# Volt_Meter_PCB_Design.net
KiCad netlist of a schematic drawn in EAGLE
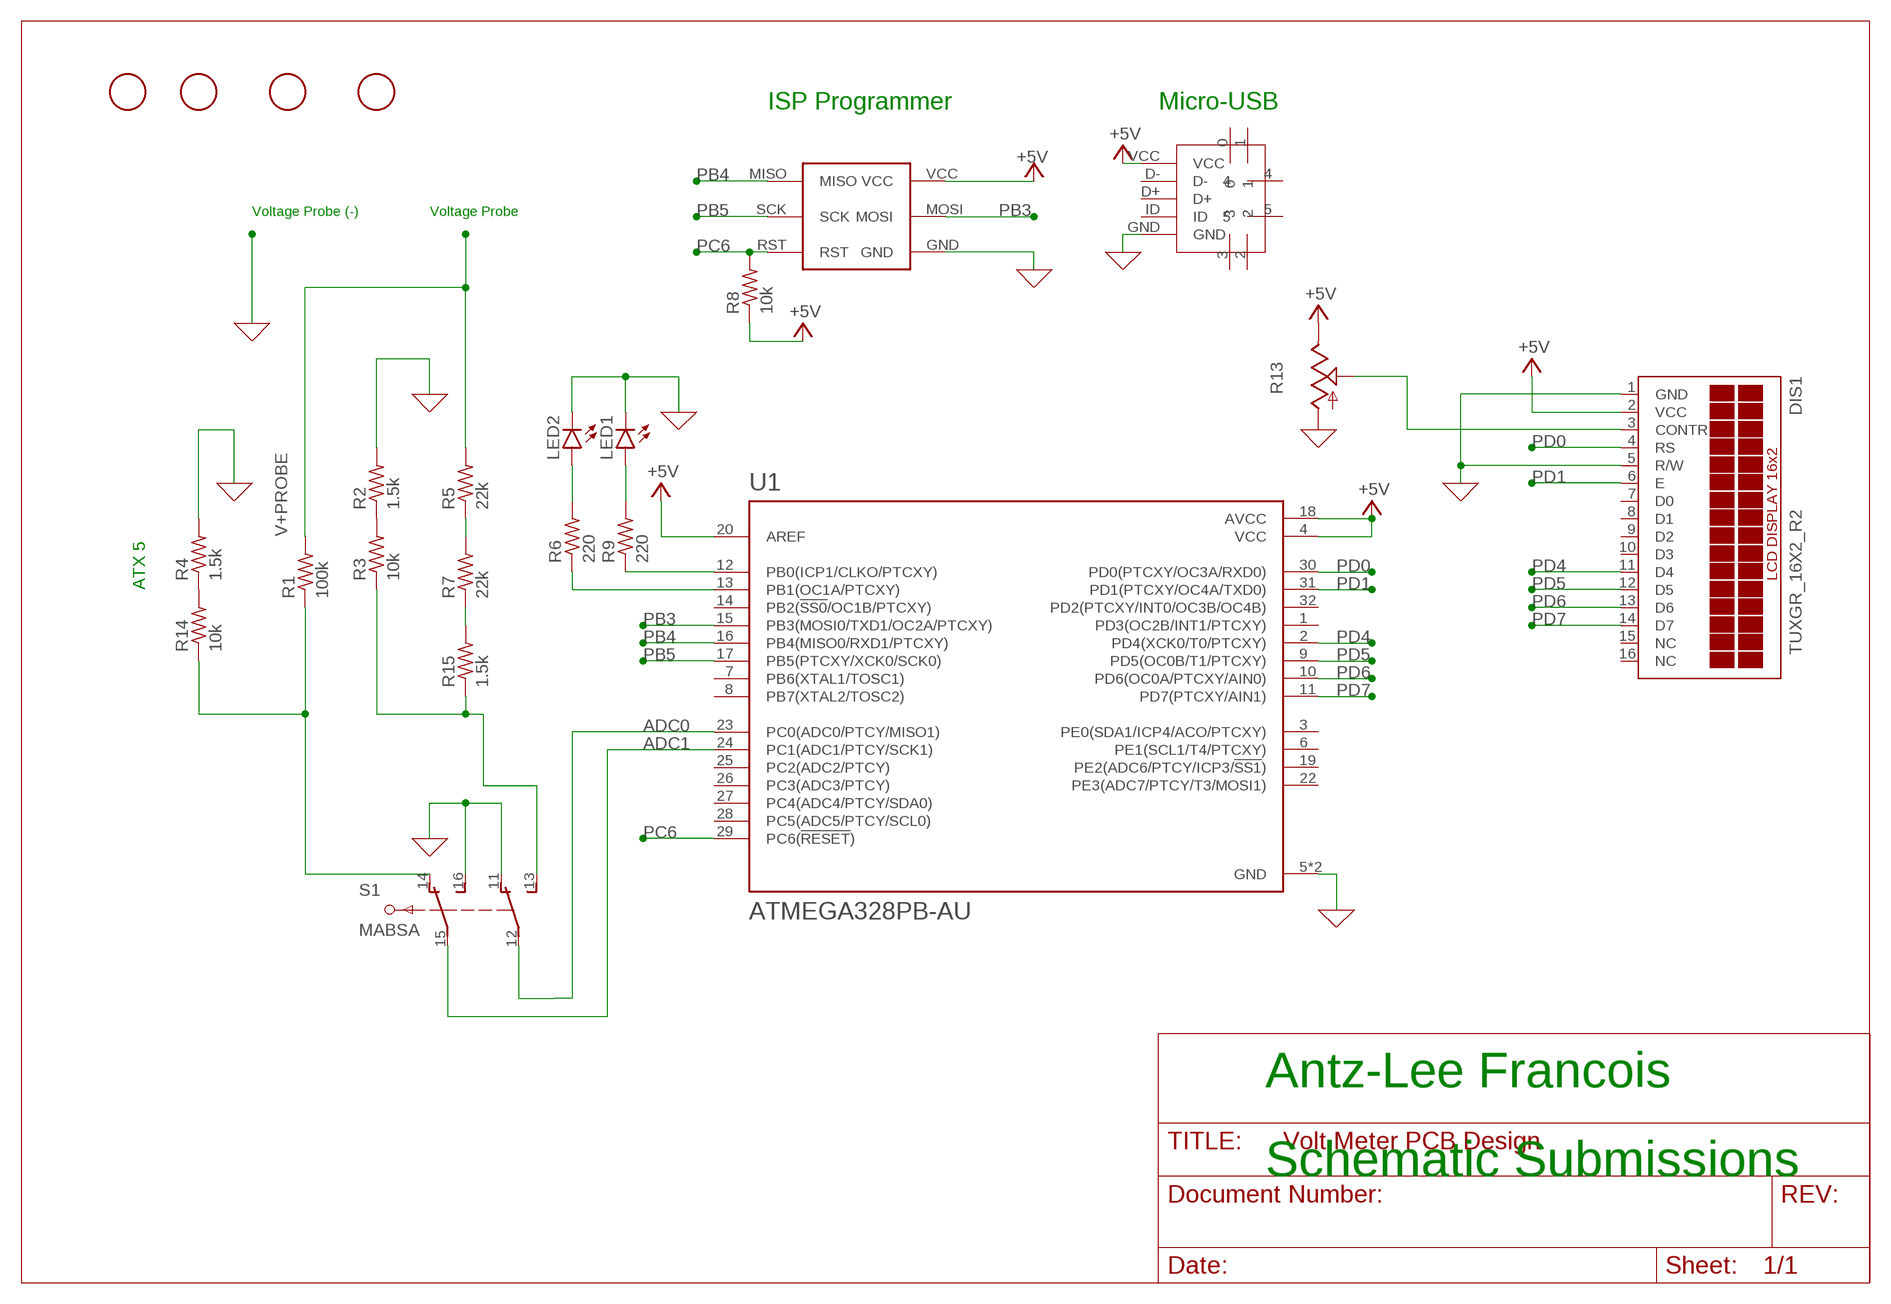
[diagram p0: schematic, sheet 1]

(export (version "E")
  (design (tool "Eeschema 10.0.6"))
  (components
    (comp (ref "AVR-ISP")
      (value "AVR-ISP")
      (footprint "eagle-import:AVR-ISP")
      (fields (field (name "MF") "Gravitech"))
      (libsource (lib "eagle-import") (part "AVR-ISP"))
    )
    (comp (ref "DIS1")
      (value "TUXGR_16X2_R2")
      (footprint "eagle-import:TUXGR_16X2_R2")
      (libsource (lib "eagle-import") (part "TUXGR_16X2_R2"))
    )
    (comp (ref "LED1")
      (value "LED5MM")
      (footprint "eagle-import:LED5MM")
      (libsource (lib "eagle-import") (part "LED5MM"))
    )
    (comp (ref "LED2")
      (value "LED5MM")
      (footprint "eagle-import:LED5MM")
      (libsource (lib "eagle-import") (part "LED5MM"))
    )
    (comp (ref "MICROUSB1")
      (value "MICROUSB1")
      (footprint "eagle-import:MICROUSB1")
      (libsource (lib "eagle-import") (part "MICROUSB1"))
    )
    (comp (ref "R1")
      (value "100k")
      (footprint "eagle-import:M0805")
      (libsource (lib "eagle-import") (part "R-US_M0805"))
    )
    (comp (ref "R2")
      (value "1.5k")
      (footprint "eagle-import:M0805")
      (libsource (lib "eagle-import") (part "R-US_M0805"))
    )
    (comp (ref "R3")
      (value "10k")
      (footprint "eagle-import:M0805")
      (libsource (lib "eagle-import") (part "R-US_M0805"))
    )
    (comp (ref "R4")
      (value "1.5k")
      (footprint "eagle-import:M0805")
      (libsource (lib "eagle-import") (part "R-US_M0805"))
    )
    (comp (ref "R5")
      (value "22k")
      (footprint "eagle-import:M0805")
      (libsource (lib "eagle-import") (part "R-US_M0805"))
    )
    (comp (ref "R6")
      (value "220")
      (footprint "eagle-import:M0805")
      (libsource (lib "eagle-import") (part "R-US_M0805"))
    )
    (comp (ref "R7")
      (value "22k")
      (footprint "eagle-import:M0805")
      (libsource (lib "eagle-import") (part "R-US_M0805"))
    )
    (comp (ref "R8")
      (value "10k")
      (footprint "eagle-import:M0805")
      (libsource (lib "eagle-import") (part "R-US_M0805"))
    )
    (comp (ref "R9")
      (value "220")
      (footprint "eagle-import:M0805")
      (libsource (lib "eagle-import") (part "R-US_M0805"))
    )
    (comp (ref "R13")
      (value "TRIM_US-B25P")
      (footprint "eagle-import:B25P")
      (libsource (lib "eagle-import") (part "TRIM_US-B25P"))
    )
    (comp (ref "R14")
      (value "10k")
      (footprint "eagle-import:M0805")
      (libsource (lib "eagle-import") (part "R-US_M0805"))
    )
    (comp (ref "R15")
      (value "1.5k")
      (footprint "eagle-import:M0805")
      (libsource (lib "eagle-import") (part "R-US_M0805"))
    )
    (comp (ref "S1")
      (value "MABSA")
      (footprint "eagle-import:MABSA")
      (libsource (lib "eagle-import") (part "MABSA"))
    )
    (comp (ref "U$1")
      (value "FIDUCIAL")
      (footprint "eagle-import:FIDUCIAL_1MM")
      (libsource (lib "eagle-import") (part "FIDUCIAL"))
    )
    (comp (ref "U$2")
      (value "FIDUCIAL")
      (footprint "eagle-import:FIDUCIAL_1MM")
      (libsource (lib "eagle-import") (part "FIDUCIAL"))
    )
    (comp (ref "U$3")
      (value "FIDUCIAL")
      (footprint "eagle-import:FIDUCIAL_1MM")
      (libsource (lib "eagle-import") (part "FIDUCIAL"))
    )
    (comp (ref "U$4")
      (value "FIDUCIAL")
      (footprint "eagle-import:FIDUCIAL_1MM")
      (libsource (lib "eagle-import") (part "FIDUCIAL"))
    )
    (comp (ref "U1")
      (value "ATMEGA328PB-AU")
      (footprint "eagle-import:QFP80P900X900X120-32N")
      (fields
        (field (name "DIGI-KEY_PART_NUMBER") "ATMEGA328PB-AURTR-ND")
        (field (name "MF") "Microchip Technology")
      )
      (libsource (lib "eagle-import") (part "ATMEGA328PB-AU"))
    )
  )
  (nets
    (net (code "1") (name "+5V") (class "Default")
      (node (ref "AVR-ISP") (pin "VCC") (pinfunction "VCC_VCC") (pintype "bidirectional"))
      (node (ref "DIS1") (pin "2") (pinfunction "VCC_2") (pintype "power_in"))
      (node (ref "MICROUSB1") (pin "VCC") (pinfunction "VCC_VCC") (pintype "bidirectional"))
      (node (ref "R13") (pin "E") (pinfunction "E_E") (pintype "passive"))
      (node (ref "R8") (pin "1") (pinfunction "1_1") (pintype "passive"))
      (node (ref "U1") (pin "18") (pinfunction "AVCC_18") (pintype "power_in"))
      (node (ref "U1") (pin "20") (pinfunction "AREF_20") (pintype "input"))
      (node (ref "U1") (pin "4") (pinfunction "VCC_4") (pintype "power_in"))
    )
    (net (code "2") (name "/ADC0") (class "Default")
      (node (ref "S1") (pin "12") (pinfunction "12_12") (pintype "passive"))
      (node (ref "U1") (pin "23") (pinfunction "PC0(ADC0/PTCY/MISO1)_23") (pintype "bidirectional"))
    )
    (net (code "3") (name "/ADC1") (class "Default")
      (node (ref "S1") (pin "15") (pinfunction "15_15") (pintype "passive"))
      (node (ref "U1") (pin "24") (pinfunction "PC1(ADC1/PTCY/SCK1)_24") (pintype "bidirectional"))
    )
    (net (code "4") (name "/PB3") (class "Default")
      (node (ref "AVR-ISP") (pin "MOSI") (pinfunction "MOSI_MOSI") (pintype "bidirectional"))
      (node (ref "U1") (pin "15") (pinfunction "PB3(MOSI0/TXD1/OC2A/PTCXY)_15") (pintype "bidirectional"))
    )
    (net (code "5") (name "/PB4") (class "Default")
      (node (ref "AVR-ISP") (pin "MISO") (pinfunction "MISO_MISO") (pintype "bidirectional"))
      (node (ref "U1") (pin "16") (pinfunction "PB4(MISO0/RXD1/PTCXY)_16") (pintype "bidirectional"))
    )
    (net (code "6") (name "/PB5") (class "Default")
      (node (ref "AVR-ISP") (pin "SCK") (pinfunction "SCK_SCK") (pintype "bidirectional"))
      (node (ref "U1") (pin "17") (pinfunction "PB5(PTCXY/XCK0/SCK0)_17") (pintype "bidirectional"))
    )
    (net (code "7") (name "/PC6") (class "Default")
      (node (ref "AVR-ISP") (pin "RST") (pinfunction "RST_RST") (pintype "bidirectional"))
      (node (ref "R8") (pin "2") (pinfunction "2_2") (pintype "passive"))
      (node (ref "U1") (pin "29") (pinfunction "PC6(~{RESET})_29") (pintype "bidirectional"))
    )
    (net (code "8") (name "/PD0") (class "Default")
      (node (ref "DIS1") (pin "4") (pinfunction "RS_4") (pintype "input"))
      (node (ref "U1") (pin "30") (pinfunction "PD0(PTCXY/OC3A/RXD0)_30") (pintype "bidirectional"))
    )
    (net (code "9") (name "/PD1") (class "Default")
      (node (ref "DIS1") (pin "6") (pinfunction "E_6") (pintype "input"))
      (node (ref "U1") (pin "31") (pinfunction "PD1(PTCXY/OC4A/TXD0)_31") (pintype "bidirectional"))
    )
    (net (code "10") (name "/PD4") (class "Default")
      (node (ref "DIS1") (pin "11") (pinfunction "D4_11") (pintype "input"))
      (node (ref "U1") (pin "2") (pinfunction "PD4(XCK0/T0/PTCXY)_2") (pintype "bidirectional"))
    )
    (net (code "11") (name "/PD5") (class "Default")
      (node (ref "DIS1") (pin "12") (pinfunction "D5_12") (pintype "input"))
      (node (ref "U1") (pin "9") (pinfunction "PD5(OC0B/T1/PTCXY)_9") (pintype "bidirectional"))
    )
    (net (code "12") (name "/PD6") (class "Default")
      (node (ref "DIS1") (pin "13") (pinfunction "D6_13") (pintype "input"))
      (node (ref "U1") (pin "10") (pinfunction "PD6(OC0A/PTCXY/AIN0)_10") (pintype "bidirectional"))
    )
    (net (code "13") (name "/PD7") (class "Default")
      (node (ref "DIS1") (pin "14") (pinfunction "D7_14") (pintype "input"))
      (node (ref "U1") (pin "11") (pinfunction "PD7(PTCXY/AIN1)_11") (pintype "bidirectional"))
    )
    (net (code "14") (name "/V+PROBE") (class "Default")
      (node (ref "R1") (pin "2") (pinfunction "2_2") (pintype "passive"))
      (node (ref "R5") (pin "2") (pinfunction "2_2") (pintype "passive"))
    )
    (net (code "15") (name "GND") (class "Default")
      (node (ref "AVR-ISP") (pin "GND") (pinfunction "GND_GND") (pintype "bidirectional"))
      (node (ref "DIS1") (pin "1") (pinfunction "GND_1") (pintype "power_in"))
      (node (ref "DIS1") (pin "5") (pinfunction "R/W_5") (pintype "input"))
      (node (ref "LED1") (pin "K") (pinfunction "C_K") (pintype "passive"))
      (node (ref "LED2") (pin "K") (pinfunction "C_K") (pintype "passive"))
      (node (ref "MICROUSB1") (pin "GND") (pinfunction "GND_GND") (pintype "bidirectional"))
      (node (ref "R13") (pin "A") (pinfunction "A_A") (pintype "passive"))
      (node (ref "R2") (pin "2") (pinfunction "2_2") (pintype "passive"))
      (node (ref "R4") (pin "2") (pinfunction "2_2") (pintype "passive"))
      (node (ref "S1") (pin "11") (pinfunction "11_11") (pintype "passive"))
      (node (ref "S1") (pin "16") (pinfunction "16_16") (pintype "passive"))
      (node (ref "U1") (pin "21") (pinfunction "GND_21") (pintype "power_in"))
      (node (ref "U1") (pin "5") (pinfunction "GND_5") (pintype "power_in"))
    )
    (net (code "16") (name "Net-(DIS1-CONTR)") (class "Default")
      (node (ref "DIS1") (pin "3") (pinfunction "CONTR_3") (pintype "input"))
      (node (ref "R13") (pin "S") (pinfunction "S_S") (pintype "passive"))
    )
    (net (code "17") (name "Net-(LED1-PadA)") (class "Default")
      (node (ref "LED1") (pin "A") (pinfunction "A_A") (pintype "passive"))
      (node (ref "R9") (pin "2") (pinfunction "2_2") (pintype "passive"))
    )
    (net (code "18") (name "Net-(LED2-PadA)") (class "Default")
      (node (ref "LED2") (pin "A") (pinfunction "A_A") (pintype "passive"))
      (node (ref "R6") (pin "2") (pinfunction "2_2") (pintype "passive"))
    )
    (net (code "19") (name "Net-(R1-Pad1)") (class "Default")
      (node (ref "R1") (pin "1") (pinfunction "1_1") (pintype "passive"))
      (node (ref "R14") (pin "1") (pinfunction "1_1") (pintype "passive"))
      (node (ref "S1") (pin "14") (pinfunction "14_14") (pintype "passive"))
    )
    (net (code "20") (name "Net-(R2-Pad1)") (class "Default")
      (node (ref "R2") (pin "1") (pinfunction "1_1") (pintype "passive"))
      (node (ref "R3") (pin "2") (pinfunction "2_2") (pintype "passive"))
    )
    (net (code "21") (name "Net-(R5-Pad1)") (class "Default")
      (node (ref "R5") (pin "1") (pinfunction "1_1") (pintype "passive"))
      (node (ref "R7") (pin "2") (pinfunction "2_2") (pintype "passive"))
    )
    (net (code "22") (name "Net-(R14-Pad2)") (class "Default")
      (node (ref "R14") (pin "2") (pinfunction "2_2") (pintype "passive"))
      (node (ref "R4") (pin "1") (pinfunction "1_1") (pintype "passive"))
    )
    (net (code "23") (name "Net-(R15-Pad1)") (class "Default")
      (node (ref "R15") (pin "1") (pinfunction "1_1") (pintype "passive"))
      (node (ref "R3") (pin "1") (pinfunction "1_1") (pintype "passive"))
      (node (ref "S1") (pin "13") (pinfunction "13_13") (pintype "passive"))
    )
    (net (code "24") (name "Net-(R15-Pad2)") (class "Default")
      (node (ref "R15") (pin "2") (pinfunction "2_2") (pintype "passive"))
      (node (ref "R7") (pin "1") (pinfunction "1_1") (pintype "passive"))
    )
    (net (code "25") (name "Net-(U1-PB0(ICP1{slash}CLKO{slash}PTCXY))") (class "Default")
      (node (ref "R9") (pin "1") (pinfunction "1_1") (pintype "passive"))
      (node (ref "U1") (pin "12") (pinfunction "PB0(ICP1/CLKO/PTCXY)_12") (pintype "bidirectional"))
    )
    (net (code "26") (name "Net-(U1-PB1(OC1A{slash}PTCXY))") (class "Default")
      (node (ref "R6") (pin "1") (pinfunction "1_1") (pintype "passive"))
      (node (ref "U1") (pin "13") (pinfunction "PB1(OC1A/PTCXY)_13") (pintype "bidirectional"))
    )
    (net (code "27") (name "unconnected-(DIS1-D0-Pad7)") (class "Default")
      (node (ref "DIS1") (pin "7") (pinfunction "D0_7") (pintype "input"))
    )
    (net (code "28") (name "unconnected-(DIS1-D1-Pad8)") (class "Default")
      (node (ref "DIS1") (pin "8") (pinfunction "D1_8") (pintype "input"))
    )
    (net (code "29") (name "unconnected-(DIS1-D2-Pad9)") (class "Default")
      (node (ref "DIS1") (pin "9") (pinfunction "D2_9") (pintype "input"))
    )
    (net (code "30") (name "unconnected-(DIS1-D3-Pad10)") (class "Default")
      (node (ref "DIS1") (pin "10") (pinfunction "D3_10") (pintype "input"))
    )
    (net (code "31") (name "unconnected-(DIS1-NC-Pad15)") (class "Default")
      (node (ref "DIS1") (pin "15") (pinfunction "NC_15") (pintype "no_connect"))
    )
    (net (code "32") (name "unconnected-(DIS1-NC-Pad16)") (class "Default")
      (node (ref "DIS1") (pin "16") (pinfunction "NC_16") (pintype "no_connect"))
    )
    (net (code "33") (name "unconnected-(MICROUSB1-Pad0)") (class "Default")
      (node (ref "MICROUSB1") (pin "0") (pinfunction "0_0") (pintype "bidirectional"))
    )
    (net (code "34") (name "unconnected-(MICROUSB1-Pad1)") (class "Default")
      (node (ref "MICROUSB1") (pin "1") (pinfunction "1_1") (pintype "bidirectional"))
    )
    (net (code "35") (name "unconnected-(MICROUSB1-Pad2)") (class "Default")
      (node (ref "MICROUSB1") (pin "2") (pinfunction "2_2") (pintype "bidirectional"))
    )
    (net (code "36") (name "unconnected-(MICROUSB1-Pad3)") (class "Default")
      (node (ref "MICROUSB1") (pin "3") (pinfunction "3_3") (pintype "bidirectional"))
    )
    (net (code "37") (name "unconnected-(MICROUSB1-Pad4)") (class "Default")
      (node (ref "MICROUSB1") (pin "4") (pinfunction "4_4") (pintype "bidirectional"))
    )
    (net (code "38") (name "unconnected-(MICROUSB1-Pad5)") (class "Default")
      (node (ref "MICROUSB1") (pin "5") (pinfunction "5_5") (pintype "bidirectional"))
    )
    (net (code "39") (name "unconnected-(MICROUSB1-PadD+)") (class "Default")
      (node (ref "MICROUSB1") (pin "D+") (pinfunction "D+_D+") (pintype "bidirectional"))
    )
    (net (code "40") (name "unconnected-(MICROUSB1-PadD-)") (class "Default")
      (node (ref "MICROUSB1") (pin "D-") (pinfunction "D-_D-") (pintype "bidirectional"))
    )
    (net (code "41") (name "unconnected-(MICROUSB1-PadID)") (class "Default")
      (node (ref "MICROUSB1") (pin "ID") (pinfunction "ID_ID") (pintype "bidirectional"))
    )
    (net (code "42") (name "unconnected-(U1-PB2(~{SS0}{slash}OC1B{slash}PTCXY)-Pad14)") (class "Default")
      (node (ref "U1") (pin "14") (pinfunction "PB2(~{SS0}/OC1B/PTCXY)_14") (pintype "bidirectional"))
    )
    (net (code "43") (name "unconnected-(U1-PB6(XTAL1{slash}TOSC1)-Pad7)") (class "Default")
      (node (ref "U1") (pin "7") (pinfunction "PB6(XTAL1/TOSC1)_7") (pintype "bidirectional"))
    )
    (net (code "44") (name "unconnected-(U1-PB7(XTAL2{slash}TOSC2)-Pad8)") (class "Default")
      (node (ref "U1") (pin "8") (pinfunction "PB7(XTAL2/TOSC2)_8") (pintype "bidirectional"))
    )
    (net (code "45") (name "unconnected-(U1-PC2(ADC2{slash}PTCY)-Pad25)") (class "Default")
      (node (ref "U1") (pin "25") (pinfunction "PC2(ADC2/PTCY)_25") (pintype "bidirectional"))
    )
    (net (code "46") (name "unconnected-(U1-PC3(ADC3{slash}PTCY)-Pad26)") (class "Default")
      (node (ref "U1") (pin "26") (pinfunction "PC3(ADC3/PTCY)_26") (pintype "bidirectional"))
    )
    (net (code "47") (name "unconnected-(U1-PC4(ADC4{slash}PTCY{slash}SDA0)-Pad27)") (class "Default")
      (node (ref "U1") (pin "27") (pinfunction "PC4(ADC4/PTCY/SDA0)_27") (pintype "bidirectional"))
    )
    (net (code "48") (name "unconnected-(U1-PC5(ADC5{slash}PTCY{slash}SCL0)-Pad28)") (class "Default")
      (node (ref "U1") (pin "28") (pinfunction "PC5(ADC5/PTCY/SCL0)_28") (pintype "bidirectional"))
    )
    (net (code "49") (name "unconnected-(U1-PD2(PTCXY{slash}INT0{slash}OC3B{slash}OC4B)-Pad32)") (class "Default")
      (node (ref "U1") (pin "32") (pinfunction "PD2(PTCXY/INT0/OC3B/OC4B)_32") (pintype "bidirectional"))
    )
    (net (code "50") (name "unconnected-(U1-PD3(OC2B{slash}INT1{slash}PTCXY)-Pad1)") (class "Default")
      (node (ref "U1") (pin "1") (pinfunction "PD3(OC2B/INT1/PTCXY)_1") (pintype "bidirectional"))
    )
    (net (code "51") (name "unconnected-(U1-PE0(SDA1{slash}ICP4{slash}ACO{slash}PTCXY)-Pad3)") (class "Default")
      (node (ref "U1") (pin "3") (pinfunction "PE0(SDA1/ICP4/ACO/PTCXY)_3") (pintype "bidirectional"))
    )
    (net (code "52") (name "unconnected-(U1-PE1(SCL1{slash}T4{slash}PTCXY)-Pad6)") (class "Default")
      (node (ref "U1") (pin "6") (pinfunction "PE1(SCL1/T4/PTCXY)_6") (pintype "bidirectional"))
    )
    (net (code "53") (name "unconnected-(U1-PE2(ADC6{slash}PTCY{slash}ICP3{slash}~{SS1})-Pad19)") (class "Default")
      (node (ref "U1") (pin "19") (pinfunction "PE2(ADC6/PTCY/ICP3/~{SS1})_19") (pintype "bidirectional"))
    )
    (net (code "54") (name "unconnected-(U1-PE3(ADC7{slash}PTCY{slash}T3{slash}MOSI1)-Pad22)") (class "Default")
      (node (ref "U1") (pin "22") (pinfunction "PE3(ADC7/PTCY/T3/MOSI1)_22") (pintype "bidirectional"))
    )
  )
)
